# fan.net
KiCad netlist of a schematic drawn in Altium Designer
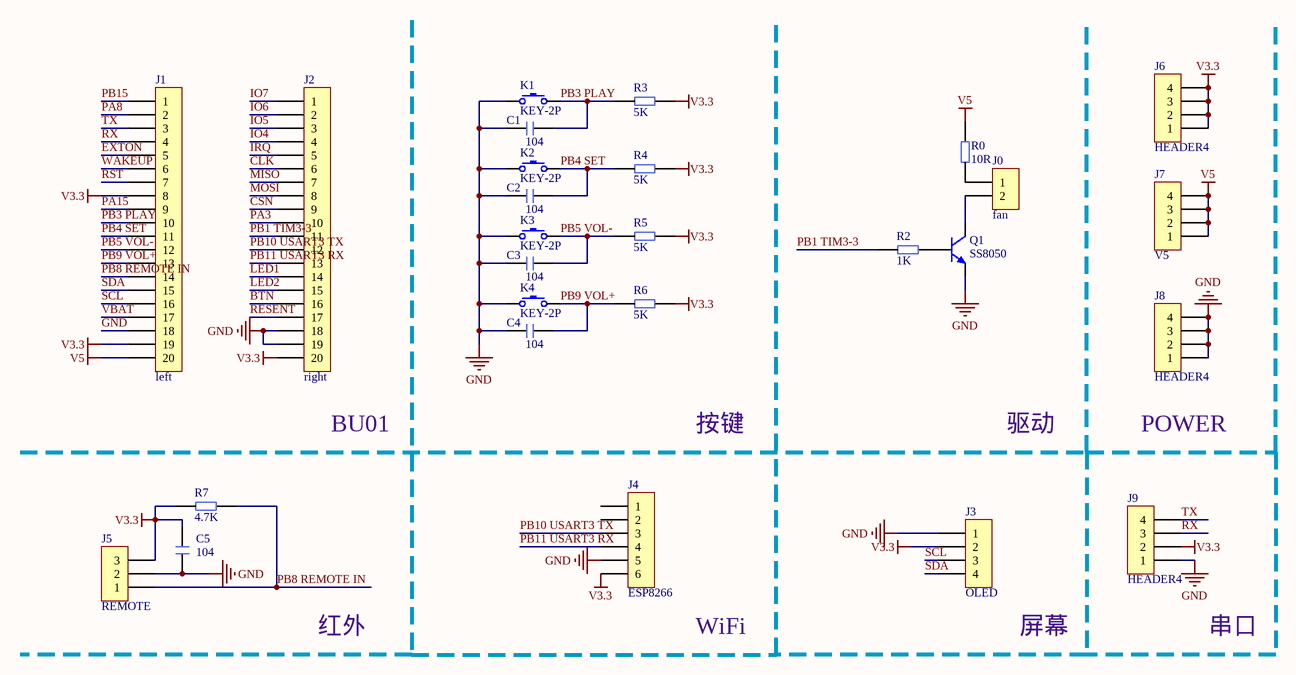
[diagram p0: fan.SchDoc]

(export (version "E")
  (design (tool "Eeschema 10.0.6"))
  (components
    (comp (ref "C1") (value "104") (footprint "C-RAD254") (libsource (lib "Minisystem") (part "CAP")))
    (comp (ref "C2") (value "104") (footprint "C-RAD254") (libsource (lib "Minisystem") (part "CAP")))
    (comp (ref "C3") (value "104") (footprint "C-RAD254") (libsource (lib "Minisystem") (part "CAP")))
    (comp (ref "C4") (value "104") (footprint "C-RAD254") (libsource (lib "Minisystem") (part "CAP")))
    (comp (ref "C5") (value "104") (footprint "C-RAD254") (libsource (lib "Minisystem") (part "CAP")))
    (comp (ref "J0")
      (value "fan")
      (footprint "PIN-2-2.54-1.0")
      (description "Connector")
      (libsource (lib "General") (part "HDR1x2"))
    )
    (comp (ref "J1")
      (value "left")
      (footprint "PIN-20-2.54-1.0")
      (description "Connector")
      (libsource (lib "General") (part "HDR1x20"))
    )
    (comp (ref "J2")
      (value "right")
      (footprint "PIN-20-2.54-1.0")
      (description "Connector")
      (libsource (lib "General") (part "HDR1x20"))
    )
    (comp (ref "J3")
      (value "OLED")
      (footprint "PIN-4-2.54-1.0")
      (description "Connector")
      (libsource (lib "General") (part "HDR1x4"))
    )
    (comp (ref "J4") (value "ESP8266") (footprint "SIP6") (libsource (lib "Minisystem") (part "HEADER6")))
    (comp (ref "J5") (value "REMOTE") (footprint "SIP3") (libsource (lib "Minisystem") (part "HEADER3")))
    (comp (ref "J6") (value "HEADER4") (footprint "SIP4") (libsource (lib "Minisystem") (part "HEADER4")))
    (comp (ref "J7") (value "V5") (footprint "SIP4") (libsource (lib "Minisystem") (part "HEADER4")))
    (comp (ref "J8") (value "HEADER4") (footprint "SIP4") (libsource (lib "Minisystem") (part "HEADER4")))
    (comp (ref "J9") (value "HEADER4") (footprint "SIP4") (libsource (lib "Minisystem") (part "HEADER4")))
    (comp (ref "K1")
      (value "KEY-2P")
      (footprint "KEY_M")
      (description "Key")
      (libsource (lib "General") (part "KEY-2P"))
    )
    (comp (ref "K2")
      (value "KEY-2P")
      (footprint "KEY_M")
      (description "Key")
      (libsource (lib "General") (part "KEY-2P"))
    )
    (comp (ref "K3")
      (value "KEY-2P")
      (footprint "KEY_M")
      (description "Key")
      (libsource (lib "General") (part "KEY-2P"))
    )
    (comp (ref "K4")
      (value "KEY-2P")
      (footprint "KEY_M")
      (description "Key")
      (libsource (lib "General") (part "KEY-2P"))
    )
    (comp (ref "Q1")
      (value "SS8050")
      (footprint "TO-92")
      (description "高频放大-NPN型")
      (libsource (lib "2、三极管") (part "8050-SMD"))
    )
    (comp (ref "R0") (value "10R") (footprint "R-AXIAL-0.4") (libsource (lib "Minisystem") (part "RES")))
    (comp (ref "R2") (value "1K") (footprint "R-AXIAL-0.4") (libsource (lib "Minisystem") (part "RES")))
    (comp (ref "R3") (value "5K") (footprint "R-AXIAL-0.4") (libsource (lib "Minisystem") (part "RES")))
    (comp (ref "R4") (value "5K") (footprint "R-AXIAL-0.4") (libsource (lib "Minisystem") (part "RES")))
    (comp (ref "R5") (value "5K") (footprint "R-AXIAL-0.4") (libsource (lib "Minisystem") (part "RES")))
    (comp (ref "R6") (value "5K") (footprint "R-AXIAL-0.4") (libsource (lib "Minisystem") (part "RES")))
    (comp (ref "R7") (value "4.7K") (footprint "R-AXIAL-0.4") (libsource (lib "Minisystem") (part "RES")))
  )
  (nets
    (net (code "1") (name "/BTN") (class "Default")
      (node (ref "J2") (pin "16") (pinfunction "16_16") (pintype "passive"))
    )
    (net (code "2") (name "/CLK") (class "Default")
      (node (ref "J2") (pin "6") (pinfunction "6_6") (pintype "passive"))
    )
    (net (code "3") (name "/CSN") (class "Default")
      (node (ref "J2") (pin "9") (pinfunction "9_9") (pintype "passive"))
    )
    (net (code "4") (name "/EXTON") (class "Default")
      (node (ref "J1") (pin "5") (pinfunction "5_5") (pintype "passive"))
    )
    (net (code "5") (name "/IO4") (class "Default")
      (node (ref "J2") (pin "4") (pinfunction "4_4") (pintype "passive"))
    )
    (net (code "6") (name "/IO5") (class "Default")
      (node (ref "J2") (pin "3") (pinfunction "3_3") (pintype "passive"))
    )
    (net (code "7") (name "/IO6") (class "Default")
      (node (ref "J2") (pin "2") (pinfunction "2_2") (pintype "passive"))
    )
    (net (code "8") (name "/IO7") (class "Default")
      (node (ref "J2") (pin "1") (pinfunction "1_1") (pintype "passive"))
    )
    (net (code "9") (name "/IRQ") (class "Default")
      (node (ref "J2") (pin "5") (pinfunction "5_5") (pintype "passive"))
    )
    (net (code "10") (name "/LED1") (class "Default")
      (node (ref "J2") (pin "14") (pinfunction "14_14") (pintype "passive"))
    )
    (net (code "11") (name "/LED2") (class "Default")
      (node (ref "J2") (pin "15") (pinfunction "15_15") (pintype "passive"))
    )
    (net (code "12") (name "/MISO") (class "Default")
      (node (ref "J2") (pin "7") (pinfunction "7_7") (pintype "passive"))
    )
    (net (code "13") (name "/MOSI") (class "Default")
      (node (ref "J2") (pin "8") (pinfunction "8_8") (pintype "passive"))
    )
    (net (code "14") (name "/PA3") (class "Default")
      (node (ref "J2") (pin "10") (pinfunction "10_10") (pintype "passive"))
    )
    (net (code "15") (name "/PA8") (class "Default")
      (node (ref "J1") (pin "2") (pinfunction "2_2") (pintype "passive"))
    )
    (net (code "16") (name "/PA15") (class "Default")
      (node (ref "J1") (pin "9") (pinfunction "9_9") (pintype "passive"))
    )
    (net (code "17") (name "/PB1 TIM3-3") (class "Default")
      (node (ref "J2") (pin "11") (pinfunction "11_11") (pintype "passive"))
      (node (ref "R2") (pin "2") (pinfunction "2_2") (pintype "passive"))
    )
    (net (code "18") (name "/PB3 PLAY") (class "Default")
      (node (ref "C1") (pin "2") (pinfunction "2_2") (pintype "passive"))
      (node (ref "J1") (pin "10") (pinfunction "10_10") (pintype "passive"))
      (node (ref "K1") (pin "2") (pinfunction "2_2") (pintype "passive"))
      (node (ref "R3") (pin "2") (pinfunction "2_2") (pintype "passive"))
    )
    (net (code "19") (name "/PB4 SET") (class "Default")
      (node (ref "C2") (pin "2") (pinfunction "2_2") (pintype "passive"))
      (node (ref "J1") (pin "11") (pinfunction "11_11") (pintype "passive"))
      (node (ref "K2") (pin "2") (pinfunction "2_2") (pintype "passive"))
      (node (ref "R4") (pin "2") (pinfunction "2_2") (pintype "passive"))
    )
    (net (code "20") (name "/PB5 VOL-") (class "Default")
      (node (ref "C3") (pin "2") (pinfunction "2_2") (pintype "passive"))
      (node (ref "J1") (pin "12") (pinfunction "12_12") (pintype "passive"))
      (node (ref "K3") (pin "2") (pinfunction "2_2") (pintype "passive"))
      (node (ref "R5") (pin "2") (pinfunction "2_2") (pintype "passive"))
    )
    (net (code "21") (name "/PB8 REMOTE IN") (class "Default")
      (node (ref "J1") (pin "14") (pinfunction "14_14") (pintype "passive"))
      (node (ref "J5") (pin "1") (pinfunction "1_1") (pintype "passive"))
      (node (ref "R7") (pin "1") (pinfunction "1_1") (pintype "passive"))
    )
    (net (code "22") (name "/PB9 VOL+") (class "Default")
      (node (ref "C4") (pin "2") (pinfunction "2_2") (pintype "passive"))
      (node (ref "J1") (pin "13") (pinfunction "13_13") (pintype "passive"))
      (node (ref "K4") (pin "2") (pinfunction "2_2") (pintype "passive"))
      (node (ref "R6") (pin "2") (pinfunction "2_2") (pintype "passive"))
    )
    (net (code "23") (name "/PB10 USART3 TX") (class "Default")
      (node (ref "J2") (pin "12") (pinfunction "12_12") (pintype "passive"))
      (node (ref "J4") (pin "3") (pinfunction "3_3") (pintype "passive"))
    )
    (net (code "24") (name "/PB11 USART3 RX") (class "Default")
      (node (ref "J2") (pin "13") (pinfunction "13_13") (pintype "passive"))
      (node (ref "J4") (pin "4") (pinfunction "4_4") (pintype "passive"))
    )
    (net (code "25") (name "/PB15") (class "Default")
      (node (ref "J1") (pin "1") (pinfunction "1_1") (pintype "passive"))
    )
    (net (code "26") (name "/RESENT") (class "Default")
      (node (ref "J2") (pin "17") (pinfunction "17_17") (pintype "passive"))
    )
    (net (code "27") (name "/RST") (class "Default")
      (node (ref "J1") (pin "7") (pinfunction "7_7") (pintype "passive"))
    )
    (net (code "28") (name "/RX") (class "Default")
      (node (ref "J1") (pin "4") (pinfunction "4_4") (pintype "passive"))
      (node (ref "J9") (pin "3") (pinfunction "3_3") (pintype "passive"))
    )
    (net (code "29") (name "/SCL") (class "Default")
      (node (ref "J1") (pin "16") (pinfunction "16_16") (pintype "passive"))
      (node (ref "J3") (pin "3") (pinfunction "3_3") (pintype "passive"))
    )
    (net (code "30") (name "/SDA") (class "Default")
      (node (ref "J1") (pin "15") (pinfunction "15_15") (pintype "passive"))
      (node (ref "J3") (pin "4") (pinfunction "4_4") (pintype "passive"))
    )
    (net (code "31") (name "/TX") (class "Default")
      (node (ref "J1") (pin "3") (pinfunction "3_3") (pintype "passive"))
      (node (ref "J9") (pin "4") (pinfunction "4_4") (pintype "passive"))
    )
    (net (code "32") (name "/VBAT") (class "Default")
      (node (ref "J1") (pin "17") (pinfunction "17_17") (pintype "passive"))
    )
    (net (code "33") (name "/WAKEUP") (class "Default")
      (node (ref "J1") (pin "6") (pinfunction "6_6") (pintype "passive"))
    )
    (net (code "34") (name "GND") (class "Default")
      (node (ref "C1") (pin "1") (pinfunction "1_1") (pintype "passive"))
      (node (ref "C2") (pin "1") (pinfunction "1_1") (pintype "passive"))
      (node (ref "C3") (pin "1") (pinfunction "1_1") (pintype "passive"))
      (node (ref "C4") (pin "1") (pinfunction "1_1") (pintype "passive"))
      (node (ref "C5") (pin "1") (pinfunction "1_1") (pintype "passive"))
      (node (ref "J1") (pin "18") (pinfunction "18_18") (pintype "passive"))
      (node (ref "J2") (pin "18") (pinfunction "18_18") (pintype "passive"))
      (node (ref "J2") (pin "19") (pinfunction "19_19") (pintype "passive"))
      (node (ref "J3") (pin "1") (pinfunction "1_1") (pintype "passive"))
      (node (ref "J4") (pin "5") (pinfunction "5_5") (pintype "passive"))
      (node (ref "J5") (pin "2") (pinfunction "2_2") (pintype "passive"))
      (node (ref "J8") (pin "1") (pinfunction "1_1") (pintype "passive"))
      (node (ref "J8") (pin "2") (pinfunction "2_2") (pintype "passive"))
      (node (ref "J8") (pin "3") (pinfunction "3_3") (pintype "passive"))
      (node (ref "J8") (pin "4") (pinfunction "4_4") (pintype "passive"))
      (node (ref "J9") (pin "1") (pinfunction "1_1") (pintype "passive"))
      (node (ref "K1") (pin "1") (pinfunction "1_1") (pintype "passive"))
      (node (ref "K2") (pin "1") (pinfunction "1_1") (pintype "passive"))
      (node (ref "K3") (pin "1") (pinfunction "1_1") (pintype "passive"))
      (node (ref "K4") (pin "1") (pinfunction "1_1") (pintype "passive"))
      (node (ref "Q1") (pin "2") (pinfunction "E_2") (pintype "passive"))
    )
    (net (code "35") (name "Net-(J0-Pad1)") (class "Default")
      (node (ref "J0") (pin "1") (pinfunction "1_1") (pintype "passive"))
      (node (ref "R0") (pin "2") (pinfunction "2_2") (pintype "passive"))
    )
    (net (code "36") (name "Net-(Q1-B)") (class "Default")
      (node (ref "Q1") (pin "1") (pinfunction "B_1") (pintype "passive"))
      (node (ref "R2") (pin "1") (pinfunction "1_1") (pintype "passive"))
    )
    (net (code "37") (name "Net-(Q1-C)") (class "Default")
      (node (ref "J0") (pin "2") (pinfunction "2_2") (pintype "passive"))
      (node (ref "Q1") (pin "3") (pinfunction "C_3") (pintype "passive"))
    )
    (net (code "38") (name "V3.3") (class "Default")
      (node (ref "C5") (pin "2") (pinfunction "2_2") (pintype "passive"))
      (node (ref "J1") (pin "19") (pinfunction "19_19") (pintype "passive"))
      (node (ref "J1") (pin "8") (pinfunction "8_8") (pintype "passive"))
      (node (ref "J2") (pin "20") (pinfunction "20_20") (pintype "passive"))
      (node (ref "J3") (pin "2") (pinfunction "2_2") (pintype "passive"))
      (node (ref "J4") (pin "6") (pinfunction "6_6") (pintype "passive"))
      (node (ref "J5") (pin "3") (pinfunction "3_3") (pintype "passive"))
      (node (ref "J6") (pin "1") (pinfunction "1_1") (pintype "passive"))
      (node (ref "J6") (pin "2") (pinfunction "2_2") (pintype "passive"))
      (node (ref "J6") (pin "3") (pinfunction "3_3") (pintype "passive"))
      (node (ref "J6") (pin "4") (pinfunction "4_4") (pintype "passive"))
      (node (ref "J9") (pin "2") (pinfunction "2_2") (pintype "passive"))
      (node (ref "R3") (pin "1") (pinfunction "1_1") (pintype "passive"))
      (node (ref "R4") (pin "1") (pinfunction "1_1") (pintype "passive"))
      (node (ref "R5") (pin "1") (pinfunction "1_1") (pintype "passive"))
      (node (ref "R6") (pin "1") (pinfunction "1_1") (pintype "passive"))
      (node (ref "R7") (pin "2") (pinfunction "2_2") (pintype "passive"))
    )
    (net (code "39") (name "V5") (class "Default")
      (node (ref "J1") (pin "20") (pinfunction "20_20") (pintype "passive"))
      (node (ref "J7") (pin "1") (pinfunction "1_1") (pintype "passive"))
      (node (ref "J7") (pin "2") (pinfunction "2_2") (pintype "passive"))
      (node (ref "J7") (pin "3") (pinfunction "3_3") (pintype "passive"))
      (node (ref "J7") (pin "4") (pinfunction "4_4") (pintype "passive"))
      (node (ref "R0") (pin "1") (pinfunction "1_1") (pintype "passive"))
    )
    (net (code "40") (name "unconnected-(J4-Pad1)") (class "Default")
      (node (ref "J4") (pin "1") (pinfunction "1_1") (pintype "passive"))
    )
    (net (code "41") (name "unconnected-(J4-Pad2)") (class "Default")
      (node (ref "J4") (pin "2") (pinfunction "2_2") (pintype "passive"))
    )
  )
)
